# ControleCarga.net
KiCad netlist of a schematic drawn in EAGLE
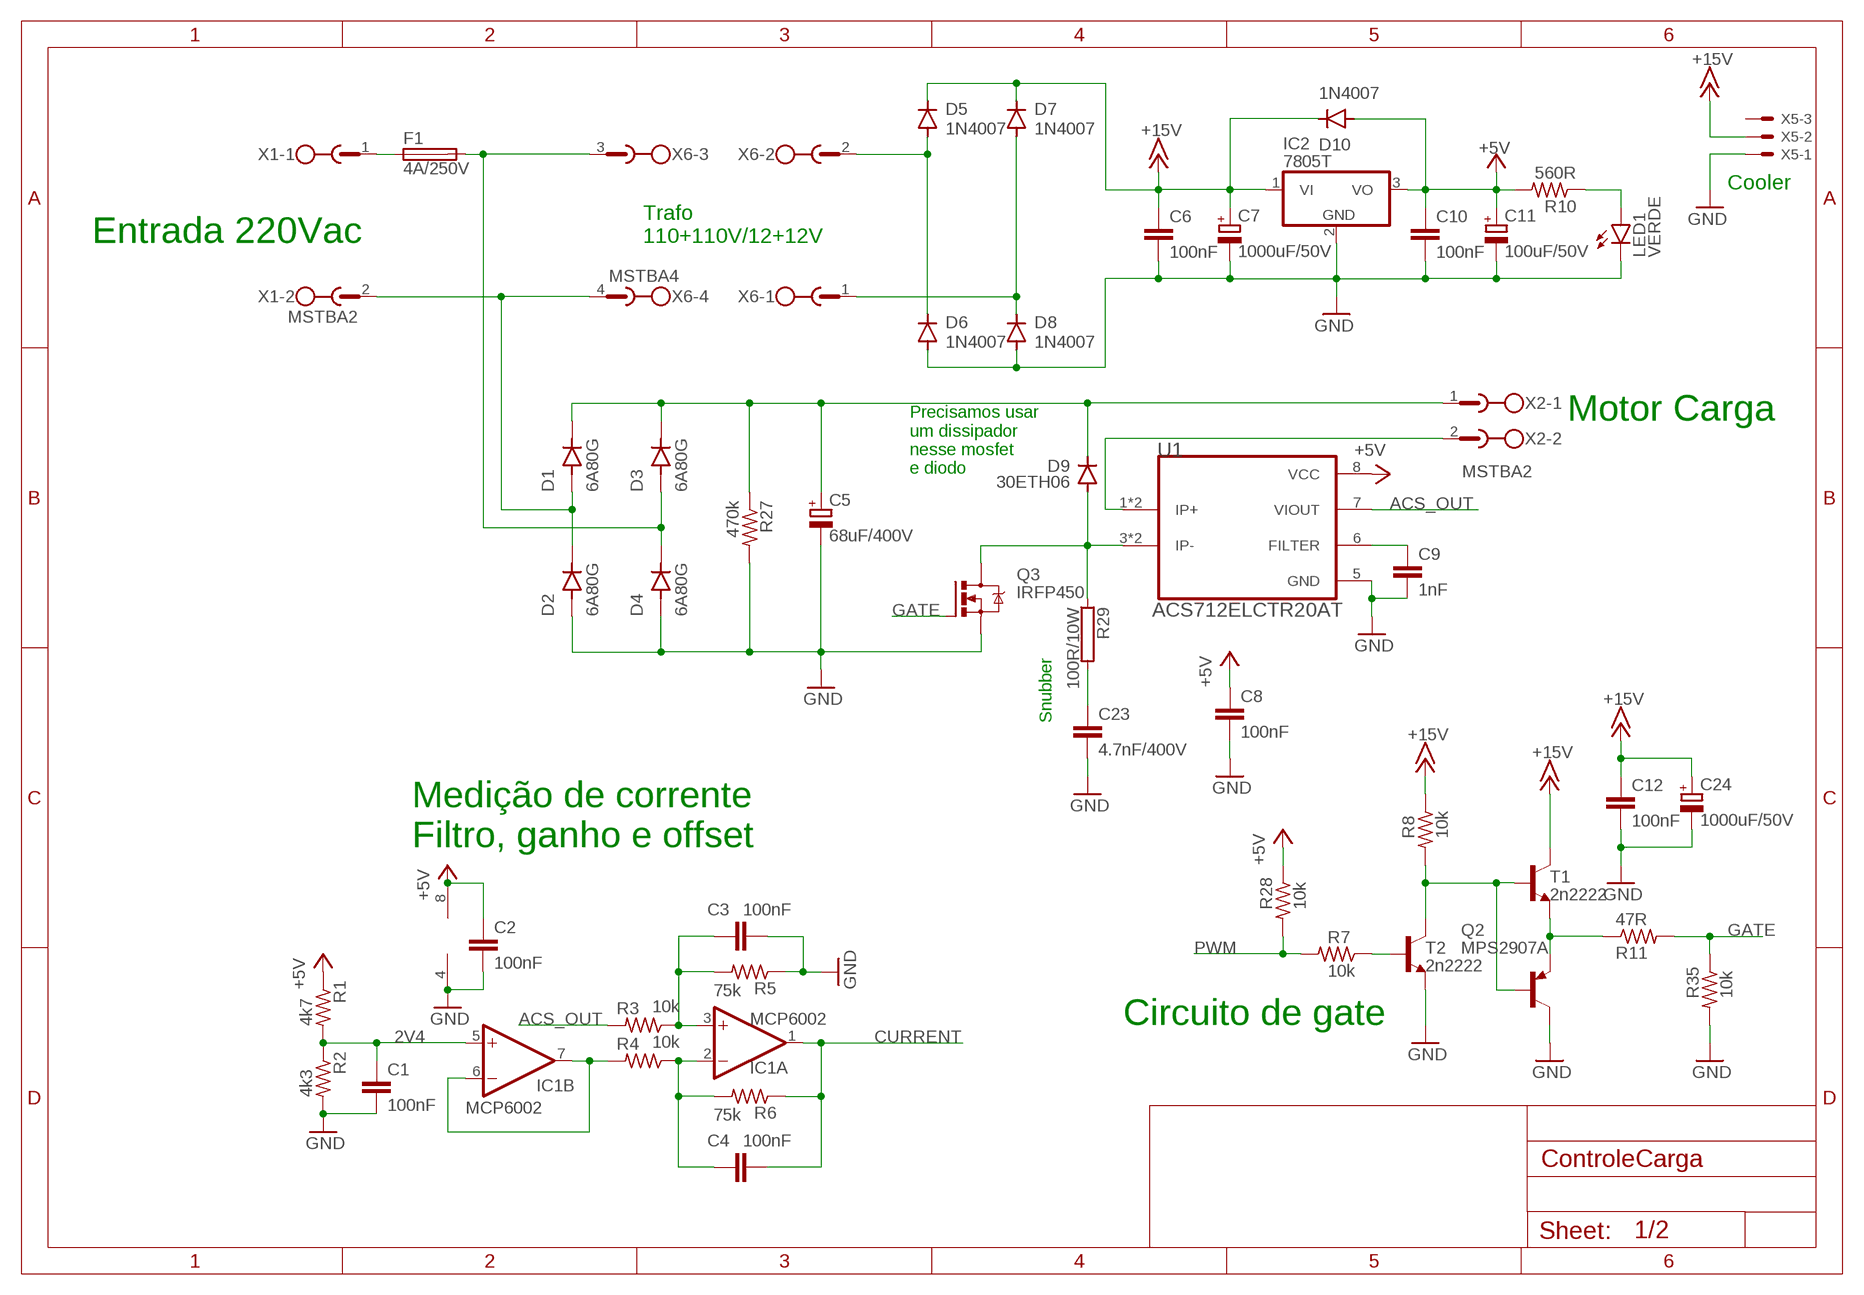
[diagram p0: schematic, sheet 1]
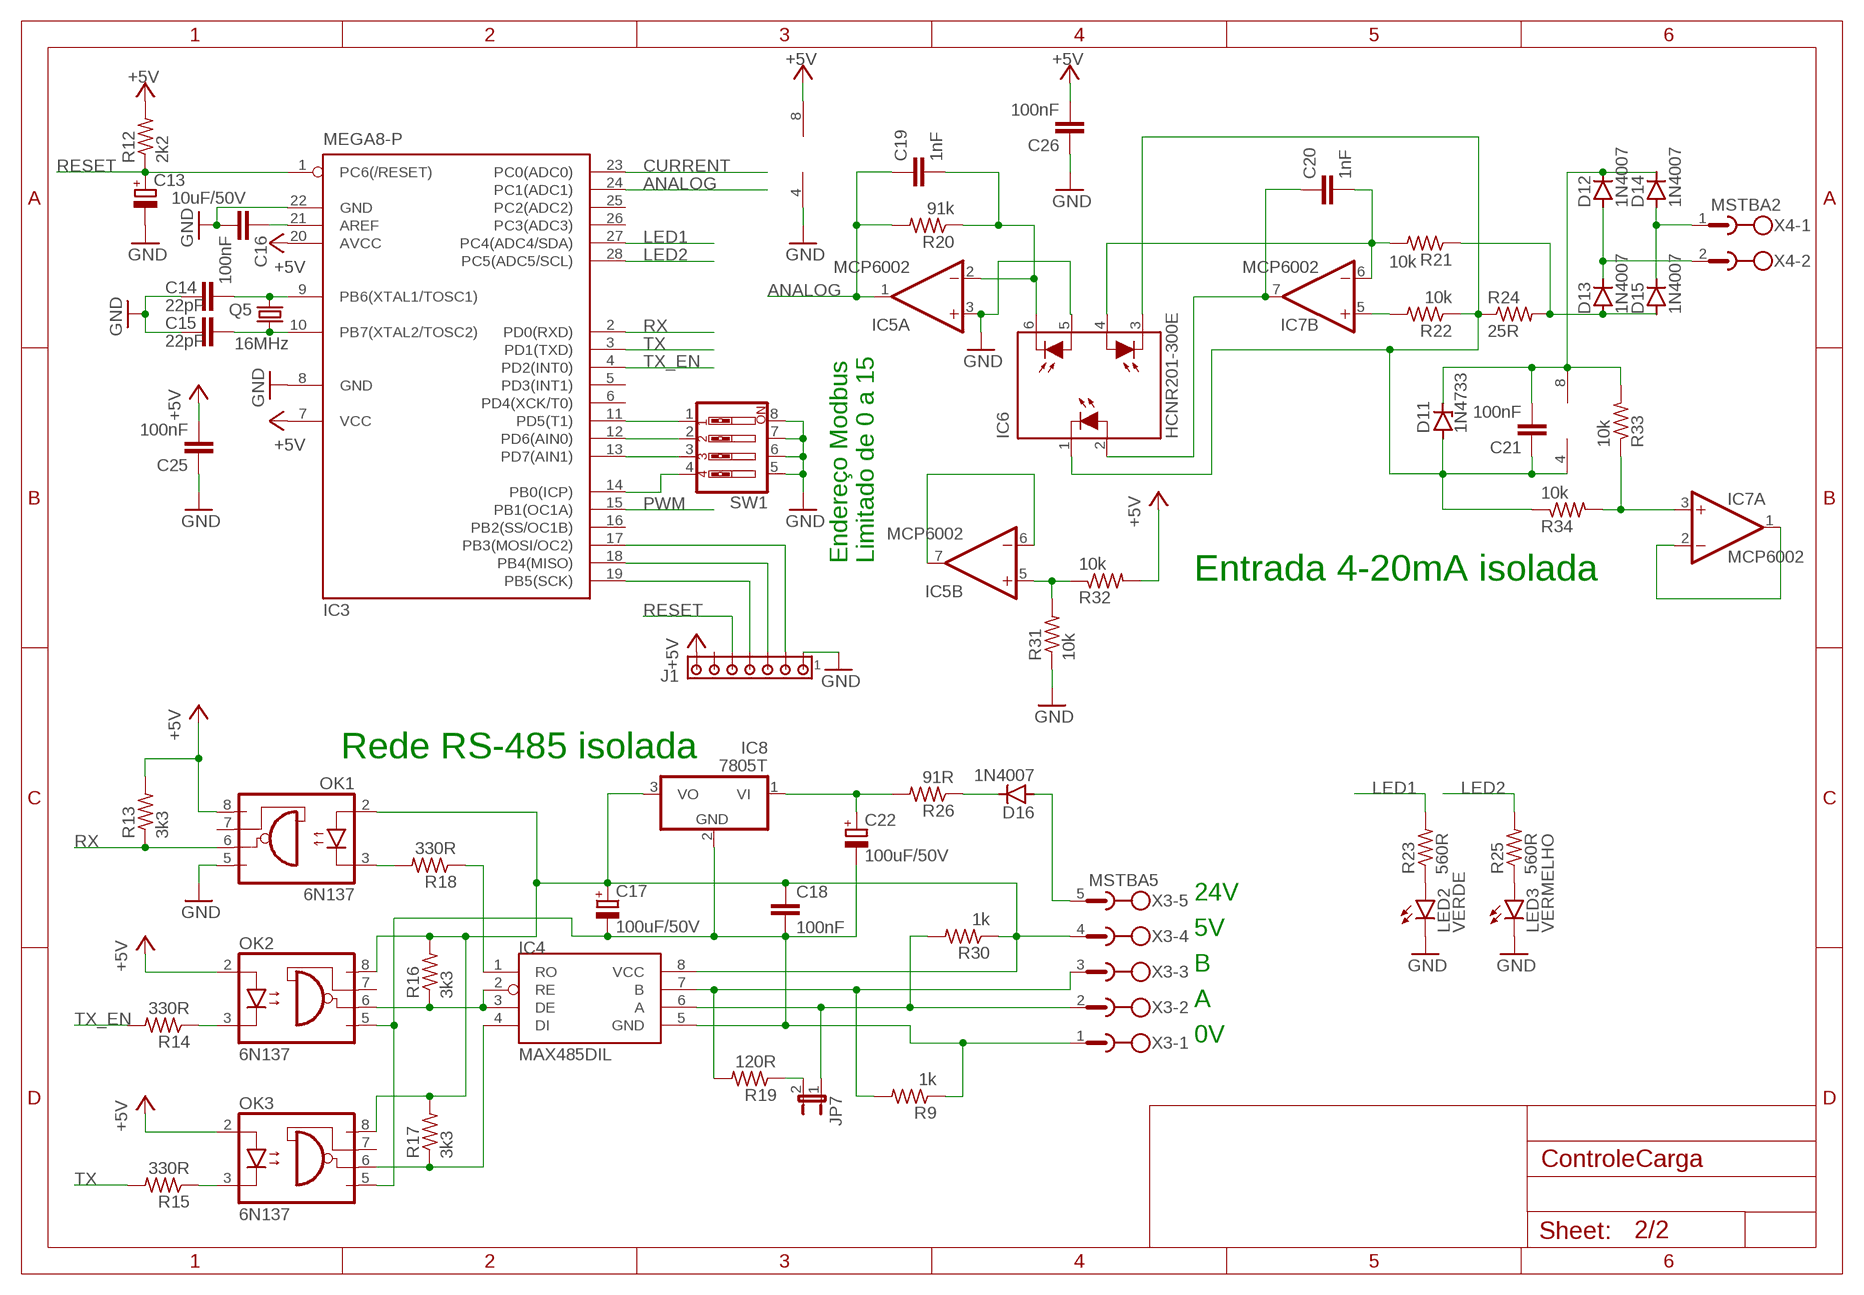
[diagram p1: schematic, sheet 2]

(export (version "E")
  (design (tool "Eeschema 10.0.6"))
  (components
    (comp (ref "C13")
      (value "10uF/50V")
      (footprint "eagle-import:E2-5")
      (libsource (lib "eagle-import") (part "CPOL-EUE2-5"))
    )
    (comp (ref "C14")
      (value "22pF")
      (footprint "eagle-import:C025-024X044")
      (libsource (lib "eagle-import") (part "C-EU025-024X044"))
    )
    (comp (ref "C15")
      (value "22pF")
      (footprint "eagle-import:C025-024X044")
      (libsource (lib "eagle-import") (part "C-EU025-024X044"))
    )
    (comp (ref "C16")
      (value "100nF")
      (footprint "eagle-import:C050-025X075")
      (libsource (lib "eagle-import") (part "C-EU050-025X075"))
    )
    (comp (ref "C17")
      (value "100uF/50V")
      (footprint "eagle-import:E3,5-8")
      (libsource (lib "eagle-import") (part "CPOL-EUE3.5-8"))
    )
    (comp (ref "C18")
      (value "100nF")
      (footprint "eagle-import:C050-025X075")
      (libsource (lib "eagle-import") (part "C-EU050-025X075"))
    )
    (comp (ref "C19")
      (value "1nF")
      (footprint "eagle-import:C025-024X044")
      (libsource (lib "eagle-import") (part "C-EU025-024X044"))
    )
    (comp (ref "C20")
      (value "1nF")
      (footprint "eagle-import:C025-024X044")
      (libsource (lib "eagle-import") (part "C-EU025-024X044"))
    )
    (comp (ref "C21")
      (value "100nF")
      (footprint "eagle-import:C050-025X075")
      (libsource (lib "eagle-import") (part "C-EU050-025X075"))
    )
    (comp (ref "C22")
      (value "100uF/50V")
      (footprint "eagle-import:E3,5-8")
      (libsource (lib "eagle-import") (part "CPOL-EUE3.5-8"))
    )
    (comp (ref "C25")
      (value "100nF")
      (footprint "eagle-import:C050-025X075")
      (libsource (lib "eagle-import") (part "C-EU050-025X075"))
    )
    (comp (ref "C26")
      (value "100nF")
      (footprint "eagle-import:C050-025X075")
      (libsource (lib "eagle-import") (part "C-EU050-025X075"))
    )
    (comp (ref "D11")
      (value "1N4733")
      (footprint "eagle-import:DO41Z10")
      (libsource (lib "eagle-import") (part "1N4728"))
    )
    (comp (ref "D12")
      (value "1N4007")
      (footprint "eagle-import:DO41-10")
      (libsource (lib "eagle-import") (part "1N4004"))
    )
    (comp (ref "D13")
      (value "1N4007")
      (footprint "eagle-import:DO41-10")
      (libsource (lib "eagle-import") (part "1N4004"))
    )
    (comp (ref "D14")
      (value "1N4007")
      (footprint "eagle-import:DO41-10")
      (libsource (lib "eagle-import") (part "1N4004"))
    )
    (comp (ref "D15")
      (value "1N4007")
      (footprint "eagle-import:DO41-10")
      (libsource (lib "eagle-import") (part "1N4004"))
    )
    (comp (ref "D16")
      (value "1N4007")
      (footprint "eagle-import:DO41-10")
      (libsource (lib "eagle-import") (part "1N4004"))
    )
    (comp (ref "IC3")
      (value "MEGA8-P")
      (footprint "eagle-import:DIL28-3")
      (libsource (lib "eagle-import") (part "MEGA8-P"))
    )
    (comp (ref "IC4")
      (value "MAX485DIL")
      (footprint "eagle-import:DIL08")
      (fields (field (name "MF") "Maxim Integrated") (field (name "MP") "MAX485"))
      (libsource (lib "eagle-import") (part "MAX485DIL"))
    )
    (comp (ref "IC5")
      (value "MCP6002")
      (footprint "eagle-import:SO08")
      (libsource (lib "eagle-import") (part "MCP602SN"))
    )
    (comp (ref "IC6")
      (value "HCNR201-300E")
      (footprint "eagle-import:DIP8-400")
      (libsource (lib "eagle-import") (part "HCNR20-300E1"))
    )
    (comp (ref "IC7")
      (value "MCP6002")
      (footprint "eagle-import:SO08")
      (libsource (lib "eagle-import") (part "MCP602SN"))
    )
    (comp (ref "IC8")
      (value "7805T")
      (footprint "eagle-import:TO220H")
      (libsource (lib "eagle-import") (part "78T05"))
    )
    (comp (ref "J1")
      (value "MTA07-100")
      (footprint "eagle-import:10X07MTA")
      (libsource (lib "eagle-import") (part "MTA07-100"))
    )
    (comp (ref "JP7")
      (value "JP1E")
      (footprint "eagle-import:JP1")
      (libsource (lib "eagle-import") (part "JP1E"))
    )
    (comp (ref "LED2")
      (value "VERDE")
      (footprint "eagle-import:LED5MM")
      (libsource (lib "eagle-import") (part "LED5MM"))
    )
    (comp (ref "LED3")
      (value "VERMELHO")
      (footprint "eagle-import:LED5MM")
      (libsource (lib "eagle-import") (part "LED5MM"))
    )
    (comp (ref "OK1")
      (value "6N137")
      (footprint "eagle-import:DIL08")
      (libsource (lib "eagle-import") (part "6N137"))
    )
    (comp (ref "OK2")
      (value "6N137")
      (footprint "eagle-import:DIL08")
      (libsource (lib "eagle-import") (part "6N137"))
    )
    (comp (ref "OK3")
      (value "6N137")
      (footprint "eagle-import:DIL08")
      (libsource (lib "eagle-import") (part "6N137"))
    )
    (comp (ref "Q5")
      (value "16MHz")
      (footprint "eagle-import:HC49_S")
      (libsource (lib "eagle-import") (part "CRYSTALHC49S"))
    )
    (comp (ref "R9")
      (value "1k")
      (footprint "eagle-import:0207_10")
      (libsource (lib "eagle-import") (part "R-US_0207/10"))
    )
    (comp (ref "R12")
      (value "2k2")
      (footprint "eagle-import:0207_10")
      (libsource (lib "eagle-import") (part "R-US_0207/10"))
    )
    (comp (ref "R13")
      (value "3k3")
      (footprint "eagle-import:0207_10")
      (libsource (lib "eagle-import") (part "R-US_0207/10"))
    )
    (comp (ref "R14")
      (value "330R")
      (footprint "eagle-import:0207_10")
      (libsource (lib "eagle-import") (part "R-US_0207/10"))
    )
    (comp (ref "R15")
      (value "330R")
      (footprint "eagle-import:0207_10")
      (libsource (lib "eagle-import") (part "R-US_0207/10"))
    )
    (comp (ref "R16")
      (value "3k3")
      (footprint "eagle-import:0207_10")
      (libsource (lib "eagle-import") (part "R-US_0207/10"))
    )
    (comp (ref "R17")
      (value "3k3")
      (footprint "eagle-import:0207_10")
      (libsource (lib "eagle-import") (part "R-US_0207/10"))
    )
    (comp (ref "R18")
      (value "330R")
      (footprint "eagle-import:0207_10")
      (libsource (lib "eagle-import") (part "R-US_0207/10"))
    )
    (comp (ref "R19")
      (value "120R")
      (footprint "eagle-import:0207_10")
      (libsource (lib "eagle-import") (part "R-US_0207/10"))
    )
    (comp (ref "R20")
      (value "91k")
      (footprint "eagle-import:0207_10")
      (libsource (lib "eagle-import") (part "R-US_0207/10"))
    )
    (comp (ref "R21")
      (value "10k")
      (footprint "eagle-import:0207_10")
      (libsource (lib "eagle-import") (part "R-US_0207/10"))
    )
    (comp (ref "R22")
      (value "10k")
      (footprint "eagle-import:0207_10")
      (libsource (lib "eagle-import") (part "R-US_0207/10"))
    )
    (comp (ref "R23")
      (value "560R")
      (footprint "eagle-import:0207_10")
      (libsource (lib "eagle-import") (part "R-US_0207/10"))
    )
    (comp (ref "R24")
      (value "25R")
      (footprint "eagle-import:0207_10")
      (libsource (lib "eagle-import") (part "R-US_0207/10"))
    )
    (comp (ref "R25")
      (value "560R")
      (footprint "eagle-import:0207_10")
      (libsource (lib "eagle-import") (part "R-US_0207/10"))
    )
    (comp (ref "R26")
      (value "91R")
      (footprint "eagle-import:0207_10")
      (libsource (lib "eagle-import") (part "R-US_0207/10"))
    )
    (comp (ref "R30")
      (value "1k")
      (footprint "eagle-import:0207_10")
      (libsource (lib "eagle-import") (part "R-US_0207/10"))
    )
    (comp (ref "R31")
      (value "10k")
      (footprint "eagle-import:0207_10")
      (libsource (lib "eagle-import") (part "R-US_0207/10"))
    )
    (comp (ref "R32")
      (value "10k")
      (footprint "eagle-import:0207_10")
      (libsource (lib "eagle-import") (part "R-US_0207/10"))
    )
    (comp (ref "R33")
      (value "10k")
      (footprint "eagle-import:0207_10")
      (libsource (lib "eagle-import") (part "R-US_0207/10"))
    )
    (comp (ref "R34")
      (value "10k")
      (footprint "eagle-import:0207_10")
      (libsource (lib "eagle-import") (part "R-US_0207/10"))
    )
    (comp (ref "SW1")
      (value "SW_DIP-4")
      (footprint "eagle-import:EDG-04")
      (libsource (lib "eagle-import") (part "SW_DIP-4"))
    )
    (comp (ref "X3")
      (value "MSTBA5")
      (footprint "eagle-import:MSTBA5")
      (fields (field (name "MPN") "1757271"))
      (libsource (lib "eagle-import") (part "MSTBA5"))
    )
    (comp (ref "X4")
      (value "MSTBA2")
      (footprint "eagle-import:MSTBA2")
      (fields (field (name "MF") "FARNELL") (field (name "MPN") "1757242"))
      (libsource (lib "eagle-import") (part "MSTBA2"))
    )
    (comp (ref "C1")
      (value "100nF")
      (footprint "eagle-import:C050-025X075")
      (libsource (lib "eagle-import") (part "C-EU050-025X075"))
    )
    (comp (ref "C2")
      (value "100nF")
      (footprint "eagle-import:C050-025X075")
      (libsource (lib "eagle-import") (part "C-EU050-025X075"))
    )
    (comp (ref "C3")
      (value "100nF")
      (footprint "eagle-import:C050-025X075")
      (libsource (lib "eagle-import") (part "C-EU050-025X075"))
    )
    (comp (ref "C4")
      (value "100nF")
      (footprint "eagle-import:C050-025X075")
      (libsource (lib "eagle-import") (part "C-EU050-025X075"))
    )
    (comp (ref "C5")
      (value "68uF/400V")
      (footprint "eagle-import:E7,5-18")
      (libsource (lib "eagle-import") (part "CPOL-EUE7.5-18"))
    )
    (comp (ref "C6")
      (value "100nF")
      (footprint "eagle-import:C050-025X075")
      (libsource (lib "eagle-import") (part "C-EU050-025X075"))
    )
    (comp (ref "C7")
      (value "1000uF/50V")
      (footprint "eagle-import:E5-13")
      (libsource (lib "eagle-import") (part "CPOL-EUE5-13"))
    )
    (comp (ref "C8")
      (value "100nF")
      (footprint "eagle-import:C050-025X075")
      (libsource (lib "eagle-import") (part "C-EU050-025X075"))
    )
    (comp (ref "C9")
      (value "1nF")
      (footprint "eagle-import:C025-024X044")
      (libsource (lib "eagle-import") (part "C-EU025-024X044"))
    )
    (comp (ref "C10")
      (value "100nF")
      (footprint "eagle-import:C050-025X075")
      (libsource (lib "eagle-import") (part "C-EU050-025X075"))
    )
    (comp (ref "C11")
      (value "100uF/50V")
      (footprint "eagle-import:E3,5-8")
      (libsource (lib "eagle-import") (part "CPOL-EUE3.5-8"))
    )
    (comp (ref "C12")
      (value "100nF")
      (footprint "eagle-import:C050-025X075")
      (libsource (lib "eagle-import") (part "C-EU050-025X075"))
    )
    (comp (ref "C23")
      (value "4.7nF/400V")
      (footprint "eagle-import:C102-043X133")
      (libsource (lib "eagle-import") (part "C-EU102-043X133"))
    )
    (comp (ref "C24")
      (value "1000uF/50V")
      (footprint "eagle-import:E5-13")
      (libsource (lib "eagle-import") (part "CPOL-EUE5-13"))
    )
    (comp (ref "D1")
      (value "6A80G")
      (footprint "eagle-import:DIOAD1950W125L885D700")
      (fields (field (name "MF") "Taiwan Semiconductor"))
      (libsource (lib "eagle-import") (part "6A80G"))
    )
    (comp (ref "D2")
      (value "6A80G")
      (footprint "eagle-import:DIOAD1950W125L885D700")
      (fields (field (name "MF") "Taiwan Semiconductor"))
      (libsource (lib "eagle-import") (part "6A80G"))
    )
    (comp (ref "D3")
      (value "6A80G")
      (footprint "eagle-import:DIOAD1950W125L885D700")
      (fields (field (name "MF") "Taiwan Semiconductor"))
      (libsource (lib "eagle-import") (part "6A80G"))
    )
    (comp (ref "D4")
      (value "6A80G")
      (footprint "eagle-import:DIOAD1950W125L885D700")
      (fields (field (name "MF") "Taiwan Semiconductor"))
      (libsource (lib "eagle-import") (part "6A80G"))
    )
    (comp (ref "D5")
      (value "1N4007")
      (footprint "eagle-import:DO41-10")
      (libsource (lib "eagle-import") (part "1N4004"))
    )
    (comp (ref "D6")
      (value "1N4007")
      (footprint "eagle-import:DO41-10")
      (libsource (lib "eagle-import") (part "1N4004"))
    )
    (comp (ref "D7")
      (value "1N4007")
      (footprint "eagle-import:DO41-10")
      (libsource (lib "eagle-import") (part "1N4004"))
    )
    (comp (ref "D8")
      (value "1N4007")
      (footprint "eagle-import:DO41-10")
      (libsource (lib "eagle-import") (part "1N4004"))
    )
    (comp (ref "D9")
      (value "30ETH06")
      (footprint "eagle-import:TO220ACS")
      (libsource (lib "eagle-import") (part "BYT08P"))
    )
    (comp (ref "D10")
      (value "1N4007")
      (footprint "eagle-import:DO41-10")
      (libsource (lib "eagle-import") (part "1N4004"))
    )
    (comp (ref "F1")
      (value "4A/250V")
      (footprint "eagle-import:SH22")
      (libsource (lib "eagle-import") (part "FUSESH22"))
    )
    (comp (ref "IC1")
      (value "MCP6002")
      (footprint "eagle-import:SO08")
      (libsource (lib "eagle-import") (part "MCP602SN"))
    )
    (comp (ref "IC2")
      (value "7805T")
      (footprint "eagle-import:TO220H")
      (libsource (lib "eagle-import") (part "78T05"))
    )
    (comp (ref "LED1")
      (value "VERDE")
      (footprint "eagle-import:LED5MM")
      (libsource (lib "eagle-import") (part "LED5MM"))
    )
    (comp (ref "Q2")
      (value "MPS2907A")
      (footprint "eagle-import:TO92-CBE")
      (libsource (lib "eagle-import") (part "MPS2907A"))
    )
    (comp (ref "Q3")
      (value "IRFP450")
      (footprint "eagle-import:TO247BV")
      (libsource (lib "eagle-import") (part "IRFPC40"))
    )
    (comp (ref "R1")
      (value "4k7")
      (footprint "eagle-import:0207_10")
      (libsource (lib "eagle-import") (part "R-US_0207/10"))
    )
    (comp (ref "R2")
      (value "4k3")
      (footprint "eagle-import:0207_10")
      (libsource (lib "eagle-import") (part "R-US_0207/10"))
    )
    (comp (ref "R3")
      (value "10k")
      (footprint "eagle-import:0207_10")
      (libsource (lib "eagle-import") (part "R-US_0207/10"))
    )
    (comp (ref "R4")
      (value "10k")
      (footprint "eagle-import:0207_10")
      (libsource (lib "eagle-import") (part "R-US_0207/10"))
    )
    (comp (ref "R5")
      (value "75k")
      (footprint "eagle-import:0207_10")
      (libsource (lib "eagle-import") (part "R-US_0207/10"))
    )
    (comp (ref "R6")
      (value "75k")
      (footprint "eagle-import:0207_10")
      (libsource (lib "eagle-import") (part "R-US_0207/10"))
    )
    (comp (ref "R7")
      (value "10k")
      (footprint "eagle-import:0207_10")
      (libsource (lib "eagle-import") (part "R-US_0207/10"))
    )
    (comp (ref "R8")
      (value "10k")
      (footprint "eagle-import:0207_10")
      (libsource (lib "eagle-import") (part "R-US_0207/10"))
    )
    (comp (ref "R10")
      (value "560R")
      (footprint "eagle-import:0207_10")
      (libsource (lib "eagle-import") (part "R-US_0207/10"))
    )
    (comp (ref "R11")
      (value "47R")
      (footprint "eagle-import:0207_10")
      (libsource (lib "eagle-import") (part "R-US_0207/10"))
    )
    (comp (ref "R27")
      (value "470k")
      (footprint "eagle-import:0207_10")
      (libsource (lib "eagle-import") (part "R-US_0207/10"))
    )
    (comp (ref "R28")
      (value "10k")
      (footprint "eagle-import:0207_10")
      (libsource (lib "eagle-import") (part "R-US_0207/10"))
    )
    (comp (ref "R29")
      (value "100R/10W")
      (footprint "eagle-import:KH216-8")
      (libsource (lib "eagle-import") (part "RKH216-8"))
    )
    (comp (ref "R35")
      (value "10k")
      (footprint "eagle-import:0207_10")
      (libsource (lib "eagle-import") (part "R-US_0207/10"))
    )
    (comp (ref "T1")
      (value "2n2222")
      (footprint "eagle-import:TO92-EBC")
      (libsource (lib "eagle-import") (part "-NPN-TO92-EBC2N2222"))
    )
    (comp (ref "T2")
      (value "2n2222")
      (footprint "eagle-import:TO92-EBC")
      (libsource (lib "eagle-import") (part "-NPN-TO92-EBC2N2222"))
    )
    (comp (ref "U1")
      (value "ACS712ELCTR20AT")
      (footprint "eagle-import:SOIC127P600X175-8N")
      (fields (field (name "MF") "Allegro") (field (name "MP") "ACS712ELCTR-30A-T"))
      (libsource (lib "eagle-import") (part "ACS712ELCTR30AT"))
    )
    (comp (ref "X1")
      (value "MSTBA2")
      (footprint "eagle-import:MSTBA2")
      (fields (field (name "MF") "FARNELL") (field (name "MPN") "1757242"))
      (libsource (lib "eagle-import") (part "MSTBA2"))
    )
    (comp (ref "X2")
      (value "MSTBA2")
      (footprint "eagle-import:MSTBA2")
      (fields (field (name "MF") "FARNELL") (field (name "MPN") "1757242"))
      (libsource (lib "eagle-import") (part "MSTBA2"))
    )
    (comp (ref "X5")
      (value "KK-156-3")
      (footprint "eagle-import:KK-156-3")
      (fields (field (name "MF") "MOLEX"))
      (libsource (lib "eagle-import") (part "KK-156-3"))
    )
    (comp (ref "X6")
      (value "MSTBA4")
      (footprint "eagle-import:MSTBA4")
      (fields (field (name "MF") "FARNELL") (field (name "MPN") "1757268"))
      (libsource (lib "eagle-import") (part "MSTBA4"))
    )
  )
  (nets
    (net (code "1") (name "+5V") (class "Default")
      (node (ref "C10") (pin "1") (pinfunction "1_1") (pintype "passive"))
      (node (ref "C11") (pin "+") (pinfunction "+_+") (pintype "passive"))
      (node (ref "C2") (pin "1") (pinfunction "1_1") (pintype "passive"))
      (node (ref "C25") (pin "2") (pinfunction "2_2") (pintype "passive"))
      (node (ref "C26") (pin "2") (pinfunction "2_2") (pintype "passive"))
      (node (ref "C8") (pin "1") (pinfunction "1_1") (pintype "passive"))
      (node (ref "D10") (pin "A") (pinfunction "A_A") (pintype "passive"))
      (node (ref "IC1") (pin "8") (pinfunction "V+_8") (pintype "power_in"))
      (node (ref "IC2") (pin "3") (pinfunction "VO_3") (pintype "passive"))
      (node (ref "IC3") (pin "20") (pinfunction "AVCC_20") (pintype "power_in"))
      (node (ref "IC3") (pin "7") (pinfunction "VCC_7") (pintype "power_in"))
      (node (ref "IC5") (pin "8") (pinfunction "V+_8") (pintype "power_in"))
      (node (ref "J1") (pin "7") (pinfunction "7_7") (pintype "passive"))
      (node (ref "OK1") (pin "8") (pinfunction "VCC_8") (pintype "passive"))
      (node (ref "OK2") (pin "2") (pinfunction "A_2") (pintype "passive"))
      (node (ref "OK3") (pin "2") (pinfunction "A_2") (pintype "passive"))
      (node (ref "R1") (pin "1") (pinfunction "1_1") (pintype "passive"))
      (node (ref "R10") (pin "2") (pinfunction "2_2") (pintype "passive"))
      (node (ref "R12") (pin "2") (pinfunction "2_2") (pintype "passive"))
      (node (ref "R13") (pin "2") (pinfunction "2_2") (pintype "passive"))
      (node (ref "R28") (pin "1") (pinfunction "1_1") (pintype "passive"))
      (node (ref "R32") (pin "2") (pinfunction "2_2") (pintype "passive"))
      (node (ref "U1") (pin "8") (pinfunction "VCC_8") (pintype "power_in"))
    )
    (net (code "2") (name "+15V") (class "Default")
      (node (ref "C12") (pin "1") (pinfunction "1_1") (pintype "passive"))
      (node (ref "C24") (pin "+") (pinfunction "+_+") (pintype "passive"))
      (node (ref "C6") (pin "1") (pinfunction "1_1") (pintype "passive"))
      (node (ref "C7") (pin "+") (pinfunction "+_+") (pintype "passive"))
      (node (ref "D10") (pin "C") (pinfunction "C_C") (pintype "passive"))
      (node (ref "D5") (pin "C") (pinfunction "C_C") (pintype "passive"))
      (node (ref "D7") (pin "C") (pinfunction "C_C") (pintype "passive"))
      (node (ref "IC2") (pin "1") (pinfunction "VI_1") (pintype "input"))
      (node (ref "R8") (pin "1") (pinfunction "1_1") (pintype "passive"))
      (node (ref "T1") (pin "C") (pinfunction "C_C") (pintype "passive"))
      (node (ref "X5") (pin "2") (pinfunction "S_2") (pintype "passive"))
    )
    (net (code "3") (name "2V4") (class "Default")
      (node (ref "C1") (pin "1") (pinfunction "1_1") (pintype "passive"))
      (node (ref "IC1") (pin "5") (pinfunction "+IN_5") (pintype "input"))
      (node (ref "R1") (pin "2") (pinfunction "2_2") (pintype "passive"))
      (node (ref "R2") (pin "1") (pinfunction "1_1") (pintype "passive"))
    )
    (net (code "4") (name "ACS_OUT") (class "Default")
      (node (ref "R3") (pin "2") (pinfunction "2_2") (pintype "passive"))
      (node (ref "U1") (pin "7") (pinfunction "VIOUT_7") (pintype "output"))
    )
    (net (code "5") (name "ANALOG") (class "Default")
      (node (ref "C19") (pin "1") (pinfunction "1_1") (pintype "passive"))
      (node (ref "IC3") (pin "24") (pinfunction "PC1(ADC1)_24") (pintype "bidirectional"))
      (node (ref "IC5") (pin "1") (pinfunction "OUT_1") (pintype "output"))
      (node (ref "R20") (pin "2") (pinfunction "2_2") (pintype "passive"))
    )
    (net (code "6") (name "CURRENT") (class "Default")
      (node (ref "C4") (pin "2") (pinfunction "2_2") (pintype "passive"))
      (node (ref "IC1") (pin "1") (pinfunction "OUT_1") (pintype "output"))
      (node (ref "IC3") (pin "23") (pinfunction "PC0(ADC0)_23") (pintype "bidirectional"))
      (node (ref "R6") (pin "1") (pinfunction "1_1") (pintype "passive"))
    )
    (net (code "7") (name "GATE") (class "Default")
      (node (ref "Q3") (pin "G") (pinfunction "G_G") (pintype "passive"))
      (node (ref "R11") (pin "2") (pinfunction "2_2") (pintype "passive"))
      (node (ref "R35") (pin "1") (pinfunction "1_1") (pintype "passive"))
    )
    (net (code "8") (name "GND") (class "Default")
      (node (ref "C1") (pin "2") (pinfunction "2_2") (pintype "passive"))
      (node (ref "C10") (pin "2") (pinfunction "2_2") (pintype "passive"))
      (node (ref "C11") (pin "-") (pinfunction "-_-") (pintype "passive"))
      (node (ref "C12") (pin "2") (pinfunction "2_2") (pintype "passive"))
      (node (ref "C13") (pin "-") (pinfunction "-_-") (pintype "passive"))
      (node (ref "C14") (pin "2") (pinfunction "2_2") (pintype "passive"))
      (node (ref "C15") (pin "2") (pinfunction "2_2") (pintype "passive"))
      (node (ref "C16") (pin "2") (pinfunction "2_2") (pintype "passive"))
      (node (ref "C2") (pin "2") (pinfunction "2_2") (pintype "passive"))
      (node (ref "C23") (pin "2") (pinfunction "2_2") (pintype "passive"))
      (node (ref "C24") (pin "-") (pinfunction "-_-") (pintype "passive"))
      (node (ref "C25") (pin "1") (pinfunction "1_1") (pintype "passive"))
      (node (ref "C26") (pin "1") (pinfunction "1_1") (pintype "passive"))
      (node (ref "C3") (pin "2") (pinfunction "2_2") (pintype "passive"))
      (node (ref "C5") (pin "-") (pinfunction "-_-") (pintype "passive"))
      (node (ref "C6") (pin "2") (pinfunction "2_2") (pintype "passive"))
      (node (ref "C7") (pin "-") (pinfunction "-_-") (pintype "passive"))
      (node (ref "C8") (pin "2") (pinfunction "2_2") (pintype "passive"))
      (node (ref "C9") (pin "2") (pinfunction "2_2") (pintype "passive"))
      (node (ref "D2") (pin "A") (pinfunction "A_A") (pintype "passive"))
      (node (ref "D4") (pin "A") (pinfunction "A_A") (pintype "passive"))
      (node (ref "D6") (pin "A") (pinfunction "A_A") (pintype "passive"))
      (node (ref "D8") (pin "A") (pinfunction "A_A") (pintype "passive"))
      (node (ref "IC1") (pin "4") (pinfunction "V-_4") (pintype "power_in"))
      (node (ref "IC2") (pin "2") (pinfunction "GND_2") (pintype "passive"))
      (node (ref "IC3") (pin "22") (pinfunction "GND_22") (pintype "power_in"))
      (node (ref "IC3") (pin "8") (pinfunction "GND_8") (pintype "power_in"))
      (node (ref "IC5") (pin "3") (pinfunction "+IN_3") (pintype "input"))
      (node (ref "IC5") (pin "4") (pinfunction "V-_4") (pintype "power_in"))
      (node (ref "IC6") (pin "5") (pinfunction "A2_5") (pintype "passive"))
      (node (ref "J1") (pin "1") (pinfunction "1_1") (pintype "passive"))
      (node (ref "LED1") (pin "K") (pinfunction "C_K") (pintype "passive"))
      (node (ref "LED2") (pin "K") (pinfunction "C_K") (pintype "passive"))
      (node (ref "LED3") (pin "K") (pinfunction "C_K") (pintype "passive"))
      (node (ref "OK1") (pin "5") (pinfunction "GND_5") (pintype "passive"))
      (node (ref "Q2") (pin "C") (pinfunction "C_C") (pintype "passive"))
      (node (ref "Q3") (pin "S") (pinfunction "S_S") (pintype "passive"))
      (node (ref "R2") (pin "2") (pinfunction "2_2") (pintype "passive"))
      (node (ref "R27") (pin "2") (pinfunction "2_2") (pintype "passive"))
      (node (ref "R31") (pin "1") (pinfunction "1_1") (pintype "passive"))
      (node (ref "R35") (pin "2") (pinfunction "2_2") (pintype "passive"))
      (node (ref "R5") (pin "1") (pinfunction "1_1") (pintype "passive"))
      (node (ref "SW1") (pin "5") (pinfunction "5_5") (pintype "passive"))
      (node (ref "SW1") (pin "6") (pinfunction "6_6") (pintype "passive"))
      (node (ref "SW1") (pin "7") (pinfunction "7_7") (pintype "passive"))
      (node (ref "SW1") (pin "8") (pinfunction "8_8") (pintype "passive"))
      (node (ref "T2") (pin "E") (pinfunction "E_E") (pintype "passive"))
      (node (ref "U1") (pin "5") (pinfunction "GND_5") (pintype "power_in"))
      (node (ref "X5") (pin "1") (pinfunction "S_1") (pintype "passive"))
    )
    (net (code "9") (name "LED1") (class "Default")
      (node (ref "IC3") (pin "27") (pinfunction "PC4(ADC4/SDA)_27") (pintype "bidirectional"))
      (node (ref "R23") (pin "2") (pinfunction "2_2") (pintype "passive"))
    )
    (net (code "10") (name "LED2") (class "Default")
      (node (ref "IC3") (pin "28") (pinfunction "PC5(ADC5/SCL)_28") (pintype "bidirectional"))
      (node (ref "R25") (pin "2") (pinfunction "2_2") (pintype "passive"))
    )
    (net (code "11") (name "Net-(C23-Pad1)") (class "Default")
      (node (ref "C23") (pin "1") (pinfunction "1_1") (pintype "passive"))
      (node (ref "R29") (pin "2") (pinfunction "2_2") (pintype "passive"))
    )
    (net (code "12") (name "Net-(D1-K)") (class "Default")
      (node (ref "C5") (pin "+") (pinfunction "+_+") (pintype "passive"))
      (node (ref "D1") (pin "C") (pinfunction "K_C") (pintype "passive"))
      (node (ref "D3") (pin "C") (pinfunction "K_C") (pintype "passive"))
      (node (ref "D9") (pin "C") (pinfunction "C_C") (pintype "passive"))
      (node (ref "R27") (pin "1") (pinfunction "1_1") (pintype "passive"))
      (node (ref "X2") (pin "1") (pinfunction "1_1") (pintype "passive"))
    )
    (net (code "13") (name "Net-(D2-K)") (class "Default")
      (node (ref "D1") (pin "A") (pinfunction "A_A") (pintype "passive"))
      (node (ref "D2") (pin "C") (pinfunction "K_C") (pintype "passive"))
      (node (ref "X1") (pin "2") (pinfunction "1_2") (pintype "passive"))
      (node (ref "X6") (pin "4") (pinfunction "1_4") (pintype "passive"))
    )
    (net (code "14") (name "Net-(D4-K)") (class "Default")
      (node (ref "D3") (pin "A") (pinfunction "A_A") (pintype "passive"))
      (node (ref "D4") (pin "C") (pinfunction "K_C") (pintype "passive"))
      (node (ref "F1") (pin "2") (pinfunction "2_2") (pintype "passive"))
      (node (ref "X6") (pin "3") (pinfunction "1_3") (pintype "passive"))
    )
    (net (code "15") (name "Net-(D7-PadA)") (class "Default")
      (node (ref "D7") (pin "A") (pinfunction "A_A") (pintype "passive"))
      (node (ref "D8") (pin "C") (pinfunction "C_C") (pintype "passive"))
      (node (ref "X6") (pin "1") (pinfunction "1_1") (pintype "passive"))
    )
    (net (code "16") (name "Net-(D9-PadA)") (class "Default")
      (node (ref "D9") (pin "A") (pinfunction "A_A") (pintype "passive"))
      (node (ref "Q3") (pin "D") (pinfunction "D_D") (pintype "passive"))
      (node (ref "R29") (pin "1") (pinfunction "1_1") (pintype "passive"))
      (node (ref "U1") (pin "3") (pinfunction "IP-_3") (pintype "input"))
      (node (ref "U1") (pin "4") (pinfunction "IP-_4") (pintype "input"))
    )
    (net (code "17") (name "Net-(D13-PadA)") (class "Default")
      (node (ref "D13") (pin "A") (pinfunction "A_A") (pintype "passive"))
      (node (ref "D15") (pin "A") (pinfunction "A_A") (pintype "passive"))
      (node (ref "R21") (pin "1") (pinfunction "1_1") (pintype "passive"))
      (node (ref "R24") (pin "2") (pinfunction "2_2") (pintype "passive"))
    )
    (net (code "18") (name "Net-(D14-PadA)") (class "Default")
      (node (ref "D14") (pin "A") (pinfunction "A_A") (pintype "passive"))
      (node (ref "D15") (pin "C") (pinfunction "C_C") (pintype "passive"))
      (node (ref "X4") (pin "1") (pinfunction "1_1") (pintype "passive"))
    )
    (net (code "19") (name "Net-(D16-PadC)") (class "Default")
      (node (ref "D16") (pin "C") (pinfunction "C_C") (pintype "passive"))
      (node (ref "R26") (pin "1") (pinfunction "1_1") (pintype "passive"))
    )
    (net (code "20") (name "Net-(F1-Pad1)") (class "Default")
      (node (ref "F1") (pin "1") (pinfunction "1_1") (pintype "passive"))
      (node (ref "X1") (pin "1") (pinfunction "1_1") (pintype "passive"))
    )
    (net (code "21") (name "Net-(IC1A-+IN)") (class "Default")
      (node (ref "C3") (pin "1") (pinfunction "1_1") (pintype "passive"))
      (node (ref "IC1") (pin "3") (pinfunction "+IN_3") (pintype "input"))
      (node (ref "R3") (pin "1") (pinfunction "1_1") (pintype "passive"))
      (node (ref "R5") (pin "2") (pinfunction "2_2") (pintype "passive"))
    )
    (net (code "22") (name "Net-(IC1A--IN)") (class "Default")
      (node (ref "C4") (pin "1") (pinfunction "1_1") (pintype "passive"))
      (node (ref "IC1") (pin "2") (pinfunction "-IN_2") (pintype "input"))
      (node (ref "R4") (pin "1") (pinfunction "1_1") (pintype "passive"))
      (node (ref "R6") (pin "2") (pinfunction "2_2") (pintype "passive"))
    )
    (net (code "23") (name "Net-(IC1B--IN)") (class "Default")
      (node (ref "IC1") (pin "6") (pinfunction "-IN_6") (pintype "input"))
      (node (ref "IC1") (pin "7") (pinfunction "OUT_7") (pintype "output"))
      (node (ref "R4") (pin "2") (pinfunction "2_2") (pintype "passive"))
    )
    (net (code "24") (name "Net-(IC3-AREF)") (class "Default")
      (node (ref "C16") (pin "1") (pinfunction "1_1") (pintype "passive"))
      (node (ref "IC3") (pin "21") (pinfunction "AREF_21") (pintype "passive"))
    )
    (net (code "25") (name "Net-(IC3-PB0(ICP))") (class "Default")
      (node (ref "IC3") (pin "14") (pinfunction "PB0(ICP)_14") (pintype "bidirectional"))
      (node (ref "SW1") (pin "4") (pinfunction "4_4") (pintype "passive"))
    )
    (net (code "26") (name "Net-(IC3-PB3(MOSI{slash}OC2))") (class "Default")
      (node (ref "IC3") (pin "17") (pinfunction "PB3(MOSI/OC2)_17") (pintype "bidirectional"))
      (node (ref "J1") (pin "2") (pinfunction "2_2") (pintype "passive"))
    )
    (net (code "27") (name "Net-(IC3-PB4(MISO))") (class "Default")
      (node (ref "IC3") (pin "18") (pinfunction "PB4(MISO)_18") (pintype "bidirectional"))
      (node (ref "J1") (pin "3") (pinfunction "3_3") (pintype "passive"))
    )
    (net (code "28") (name "Net-(IC3-PB5(SCK))") (class "Default")
      (node (ref "IC3") (pin "19") (pinfunction "PB5(SCK)_19") (pintype "bidirectional"))
      (node (ref "J1") (pin "4") (pinfunction "4_4") (pintype "passive"))
    )
    (net (code "29") (name "Net-(IC3-PB6(XTAL1{slash}TOSC1))") (class "Default")
      (node (ref "C14") (pin "1") (pinfunction "1_1") (pintype "passive"))
      (node (ref "IC3") (pin "9") (pinfunction "PB6(XTAL1/TOSC1)_9") (pintype "bidirectional"))
      (node (ref "Q5") (pin "2") (pinfunction "2_2") (pintype "passive"))
    )
    (net (code "30") (name "Net-(IC3-PB7(XTAL2{slash}TOSC2))") (class "Default")
      (node (ref "C15") (pin "1") (pinfunction "1_1") (pintype "passive"))
      (node (ref "IC3") (pin "10") (pinfunction "PB7(XTAL2/TOSC2)_10") (pintype "bidirectional"))
      (node (ref "Q5") (pin "1") (pinfunction "1_1") (pintype "passive"))
    )
    (net (code "31") (name "Net-(IC3-PD5(T1))") (class "Default")
      (node (ref "IC3") (pin "11") (pinfunction "PD5(T1)_11") (pintype "bidirectional"))
      (node (ref "SW1") (pin "1") (pinfunction "1_1") (pintype "passive"))
    )
    (net (code "32") (name "Net-(IC3-PD6(AIN0))") (class "Default")
      (node (ref "IC3") (pin "12") (pinfunction "PD6(AIN0)_12") (pintype "bidirectional"))
      (node (ref "SW1") (pin "2") (pinfunction "2_2") (pintype "passive"))
    )
    (net (code "33") (name "Net-(IC3-PD7(AIN1))") (class "Default")
      (node (ref "IC3") (pin "13") (pinfunction "PD7(AIN1)_13") (pintype "bidirectional"))
      (node (ref "SW1") (pin "3") (pinfunction "3_3") (pintype "passive"))
    )
    (net (code "34") (name "Net-(IC4-A)") (class "Default")
      (node (ref "IC4") (pin "6") (pinfunction "A_6") (pintype "bidirectional"))
      (node (ref "JP7") (pin "1") (pinfunction "1_1") (pintype "passive"))
      (node (ref "R30") (pin "2") (pinfunction "2_2") (pintype "passive"))
      (node (ref "X3") (pin "2") (pinfunction "1_2") (pintype "passive"))
    )
    (net (code "35") (name "Net-(IC4-B)") (class "Default")
      (node (ref "IC4") (pin "7") (pinfunction "B_7") (pintype "bidirectional"))
      (node (ref "R19") (pin "2") (pinfunction "2_2") (pintype "passive"))
      (node (ref "R9") (pin "2") (pinfunction "2_2") (pintype "passive"))
      (node (ref "X3") (pin "3") (pinfunction "1_3") (pintype "passive"))
    )
    (net (code "36") (name "Net-(IC4-DE)") (class "Default")
      (node (ref "IC4") (pin "2") (pinfunction "RE_2") (pintype "bidirectional"))
      (node (ref "IC4") (pin "3") (pinfunction "DE_3") (pintype "bidirectional"))
      (node (ref "OK2") (pin "6") (pinfunction "VO_6") (pintype "passive"))
      (node (ref "R16") (pin "1") (pinfunction "1_1") (pintype "passive"))
    )
    (net (code "37") (name "Net-(IC4-DI)") (class "Default")
      (node (ref "IC4") (pin "4") (pinfunction "DI_4") (pintype "bidirectional"))
      (node (ref "OK3") (pin "6") (pinfunction "VO_6") (pintype "passive"))
      (node (ref "R17") (pin "1") (pinfunction "1_1") (pintype "passive"))
    )
    (net (code "38") (name "Net-(IC4-GND)") (class "Default")
      (node (ref "C17") (pin "-") (pinfunction "-_-") (pintype "passive"))
      (node (ref "C18") (pin "2") (pinfunction "2_2") (pintype "passive"))
      (node (ref "C22") (pin "-") (pinfunction "-_-") (pintype "passive"))
      (node (ref "IC4") (pin "5") (pinfunction "GND_5") (pintype "bidirectional"))
      (node (ref "IC8") (pin "2") (pinfunction "GND_2") (pintype "passive"))
      (node (ref "OK2") (pin "5") (pinfunction "GND_5") (pintype "passive"))
      (node (ref "OK3") (pin "5") (pinfunction "GND_5") (pintype "passive"))
      (node (ref "R9") (pin "1") (pinfunction "1_1") (pintype "passive"))
      (node (ref "X3") (pin "1") (pinfunction "1_1") (pintype "passive"))
    )
    (net (code "39") (name "Net-(IC4-RO)") (class "Default")
      (node (ref "IC4") (pin "1") (pinfunction "RO_1") (pintype "bidirectional"))
      (node (ref "R18") (pin "1") (pinfunction "1_1") (pintype "passive"))
    )
    (net (code "40") (name "Net-(IC4-VCC)") (class "Default")
      (node (ref "C17") (pin "+") (pinfunction "+_+") (pintype "passive"))
      (node (ref "C18") (pin "1") (pinfunction "1_1") (pintype "passive"))
      (node (ref "IC4") (pin "8") (pinfunction "VCC_8") (pintype "bidirectional"))
      (node (ref "IC8") (pin "3") (pinfunction "VO_3") (pintype "passive"))
      (node (ref "OK1") (pin "2") (pinfunction "A_2") (pintype "passive"))
      (node (ref "OK2") (pin "8") (pinfunction "VCC_8") (pintype "passive"))
      (node (ref "OK3") (pin "8") (pinfunction "VCC_8") (pintype "passive"))
      (node (ref "R16") (pin "2") (pinfunction "2_2") (pintype "passive"))
      (node (ref "R17") (pin "2") (pinfunction "2_2") (pintype "passive"))
      (node (ref "R30") (pin "1") (pinfunction "1_1") (pintype "passive"))
      (node (ref "X3") (pin "4") (pinfunction "1_4") (pintype "passive"))
    )
    (net (code "41") (name "Net-(IC5A--IN)") (class "Default")
      (node (ref "C19") (pin "2") (pinfunction "2_2") (pintype "passive"))
      (node (ref "IC5") (pin "2") (pinfunction "-IN_2") (pintype "input"))
      (node (ref "IC6") (pin "6") (pinfunction "C2_6") (pintype "passive"))
      (node (ref "R20") (pin "1") (pinfunction "1_1") (pintype "passive"))
    )
    (net (code "42") (name "Net-(IC5B-+IN)") (class "Default")
      (node (ref "IC5") (pin "5") (pinfunction "+IN_5") (pintype "input"))
      (node (ref "R31") (pin "2") (pinfunction "2_2") (pintype "passive"))
      (node (ref "R32") (pin "1") (pinfunction "1_1") (pintype "passive"))
    )
    (net (code "43") (name "Net-(IC5B--IN)") (class "Default")
      (node (ref "IC5") (pin "6") (pinfunction "-IN_6") (pintype "input"))
      (node (ref "IC5") (pin "7") (pinfunction "OUT_7") (pintype "output"))
    )
    (net (code "44") (name "Net-(IC6-A)") (class "Default")
      (node (ref "C20") (pin "1") (pinfunction "1_1") (pintype "passive"))
      (node (ref "IC6") (pin "2") (pinfunction "A_2") (pintype "passive"))
      (node (ref "IC7") (pin "7") (pinfunction "OUT_7") (pintype "output"))
    )
    (net (code "45") (name "Net-(IC6-A1)") (class "Default")
      (node (ref "C20") (pin "2") (pinfunction "2_2") (pintype "passive"))
      (node (ref "IC6") (pin "4") (pinfunction "A1_4") (pintype "passive"))
      (node (ref "IC7") (pin "6") (pinfunction "-IN_6") (pintype "input"))
      (node (ref "R21") (pin "2") (pinfunction "2_2") (pintype "passive"))
    )
    (net (code "46") (name "Net-(IC6-C)") (class "Default")
      (node (ref "C21") (pin "1") (pinfunction "1_1") (pintype "passive"))
      (node (ref "D11") (pin "A") (pinfunction "A_A") (pintype "passive"))
      (node (ref "IC6") (pin "1") (pinfunction "C_1") (pintype "passive"))
      (node (ref "IC6") (pin "3") (pinfunction "C1_3") (pintype "passive"))
      (node (ref "IC7") (pin "4") (pinfunction "V-_4") (pintype "power_in"))
      (node (ref "R22") (pin "1") (pinfunction "1_1") (pintype "passive"))
      (node (ref "R24") (pin "1") (pinfunction "1_1") (pintype "passive"))
      (node (ref "R34") (pin "1") (pinfunction "1_1") (pintype "passive"))
    )
    (net (code "47") (name "Net-(IC7A-+IN)") (class "Default")
      (node (ref "IC7") (pin "3") (pinfunction "+IN_3") (pintype "input"))
      (node (ref "R33") (pin "1") (pinfunction "1_1") (pintype "passive"))
      (node (ref "R34") (pin "2") (pinfunction "2_2") (pintype "passive"))
    )
    (net (code "48") (name "Net-(IC7A--IN)") (class "Default")
      (node (ref "IC7") (pin "1") (pinfunction "OUT_1") (pintype "output"))
      (node (ref "IC7") (pin "2") (pinfunction "-IN_2") (pintype "input"))
    )
    (net (code "49") (name "Net-(IC7B-+IN)") (class "Default")
      (node (ref "IC7") (pin "5") (pinfunction "+IN_5") (pintype "input"))
      (node (ref "R22") (pin "2") (pinfunction "2_2") (pintype "passive"))
    )
    (net (code "50") (name "Net-(IC7C-V+)") (class "Default")
      (node (ref "C21") (pin "2") (pinfunction "2_2") (pintype "passive"))
      (node (ref "D11") (pin "C") (pinfunction "C_C") (pintype "passive"))
      (node (ref "D12") (pin "C") (pinfunction "C_C") (pintype "passive"))
      (node (ref "D14") (pin "C") (pinfunction "C_C") (pintype "passive"))
      (node (ref "IC7") (pin "8") (pinfunction "V+_8") (pintype "power_in"))
      (node (ref "R33") (pin "2") (pinfunction "2_2") (pintype "passive"))
    )
    (net (code "51") (name "Net-(IC8-VI)") (class "Default")
      (node (ref "C22") (pin "+") (pinfunction "+_+") (pintype "passive"))
      (node (ref "IC8") (pin "1") (pinfunction "VI_1") (pintype "input"))
      (node (ref "R26") (pin "2") (pinfunction "2_2") (pintype "passive"))
    )
    (net (code "52") (name "Net-(JP7-Pad2)") (class "Default")
      (node (ref "JP7") (pin "2") (pinfunction "2_2") (pintype "passive"))
      (node (ref "R19") (pin "1") (pinfunction "1_1") (pintype "passive"))
    )
    (net (code "53") (name "Net-(LED1-PadA)") (class "Default")
      (node (ref "LED1") (pin "A") (pinfunction "A_A") (pintype "passive"))
      (node (ref "R10") (pin "1") (pinfunction "1_1") (pintype "passive"))
    )
    (net (code "54") (name "Net-(LED2-PadA)") (class "Default")
      (node (ref "LED2") (pin "A") (pinfunction "A_A") (pintype "passive"))
      (node (ref "R23") (pin "1") (pinfunction "1_1") (pintype "passive"))
    )
    (net (code "55") (name "Net-(LED3-PadA)") (class "Default")
      (node (ref "LED3") (pin "A") (pinfunction "A_A") (pintype "passive"))
      (node (ref "R25") (pin "1") (pinfunction "1_1") (pintype "passive"))
    )
    (net (code "56") (name "Net-(OK1-C)") (class "Default")
      (node (ref "OK1") (pin "3") (pinfunction "C_3") (pintype "passive"))
      (node (ref "R18") (pin "2") (pinfunction "2_2") (pintype "passive"))
    )
    (net (code "57") (name "Net-(OK2-C)") (class "Default")
      (node (ref "OK2") (pin "3") (pinfunction "C_3") (pintype "passive"))
      (node (ref "R14") (pin "1") (pinfunction "1_1") (pintype "passive"))
    )
    (net (code "58") (name "Net-(OK3-C)") (class "Default")
      (node (ref "OK3") (pin "3") (pinfunction "C_3") (pintype "passive"))
      (node (ref "R15") (pin "1") (pinfunction "1_1") (pintype "passive"))
    )
    (net (code "59") (name "Net-(Q2-PadB)") (class "Default")
      (node (ref "Q2") (pin "B") (pinfunction "B_B") (pintype "passive"))
      (node (ref "R8") (pin "2") (pinfunction "2_2") (pintype "passive"))
      (node (ref "T1") (pin "B") (pinfunction "B_B") (pintype "passive"))
      (node (ref "T2") (pin "C") (pinfunction "C_C") (pintype "passive"))
    )
    (net (code "60") (name "Net-(Q2-PadE)") (class "Default")
      (node (ref "Q2") (pin "E") (pinfunction "E_E") (pintype "passive"))
      (node (ref "R11") (pin "1") (pinfunction "1_1") (pintype "passive"))
      (node (ref "T1") (pin "E") (pinfunction "E_E") (pintype "passive"))
    )
    (net (code "61") (name "Net-(R7-Pad1)") (class "Default")
      (node (ref "R7") (pin "1") (pinfunction "1_1") (pintype "passive"))
      (node (ref "T2") (pin "B") (pinfunction "B_B") (pintype "passive"))
    )
    (net (code "62") (name "Net-(U1-FILTER)") (class "Default")
      (node (ref "C9") (pin "1") (pinfunction "1_1") (pintype "passive"))
      (node (ref "U1") (pin "6") (pinfunction "FILTER_6") (pintype "passive"))
    )
    (net (code "63") (name "Net-(X2B-1)") (class "Default")
      (node (ref "U1") (pin "1") (pinfunction "IP+_1") (pintype "input"))
      (node (ref "U1") (pin "2") (pinfunction "IP+_2") (pintype "input"))
      (node (ref "X2") (pin "2") (pinfunction "1_2") (pintype "passive"))
    )
    (net (code "64") (name "Net-(X3E-1)") (class "Default")
      (node (ref "D16") (pin "A") (pinfunction "A_A") (pintype "passive"))
      (node (ref "X3") (pin "5") (pinfunction "1_5") (pintype "passive"))
    )
    (net (code "65") (name "Net-(X4B-1)") (class "Default")
      (node (ref "D12") (pin "A") (pinfunction "A_A") (pintype "passive"))
      (node (ref "D13") (pin "C") (pinfunction "C_C") (pintype "passive"))
      (node (ref "X4") (pin "2") (pinfunction "1_2") (pintype "passive"))
    )
    (net (code "66") (name "Net-(X6B-1)") (class "Default")
      (node (ref "D5") (pin "A") (pinfunction "A_A") (pintype "passive"))
      (node (ref "D6") (pin "C") (pinfunction "C_C") (pintype "passive"))
      (node (ref "X6") (pin "2") (pinfunction "1_2") (pintype "passive"))
    )
    (net (code "67") (name "PWM") (class "Default")
      (node (ref "IC3") (pin "15") (pinfunction "PB1(OC1A)_15") (pintype "bidirectional"))
      (node (ref "R28") (pin "2") (pinfunction "2_2") (pintype "passive"))
      (node (ref "R7") (pin "2") (pinfunction "2_2") (pintype "passive"))
    )
    (net (code "68") (name "RESET") (class "Default")
      (node (ref "C13") (pin "+") (pinfunction "+_+") (pintype "passive"))
      (node (ref "IC3") (pin "1") (pinfunction "PC6(/RESET)_1") (pintype "bidirectional"))
      (node (ref "J1") (pin "5") (pinfunction "5_5") (pintype "passive"))
      (node (ref "R12") (pin "1") (pinfunction "1_1") (pintype "passive"))
    )
    (net (code "69") (name "RX") (class "Default")
      (node (ref "IC3") (pin "2") (pinfunction "PD0(RXD)_2") (pintype "bidirectional"))
      (node (ref "OK1") (pin "6") (pinfunction "VO_6") (pintype "passive"))
      (node (ref "R13") (pin "1") (pinfunction "1_1") (pintype "passive"))
    )
    (net (code "70") (name "TX") (class "Default")
      (node (ref "IC3") (pin "3") (pinfunction "PD1(TXD)_3") (pintype "bidirectional"))
      (node (ref "R15") (pin "2") (pinfunction "2_2") (pintype "passive"))
    )
    (net (code "71") (name "TX_EN") (class "Default")
      (node (ref "IC3") (pin "4") (pinfunction "PD2(INT0)_4") (pintype "bidirectional"))
      (node (ref "R14") (pin "2") (pinfunction "2_2") (pintype "passive"))
    )
    (net (code "72") (name "unconnected-(IC3-PB2(SS{slash}OC1B)-Pad16)") (class "Default")
      (node (ref "IC3") (pin "16") (pinfunction "PB2(SS/OC1B)_16") (pintype "bidirectional"))
    )
    (net (code "73") (name "unconnected-(IC3-PC2(ADC2)-Pad25)") (class "Default")
      (node (ref "IC3") (pin "25") (pinfunction "PC2(ADC2)_25") (pintype "bidirectional"))
    )
    (net (code "74") (name "unconnected-(IC3-PC3(ADC3)-Pad26)") (class "Default")
      (node (ref "IC3") (pin "26") (pinfunction "PC3(ADC3)_26") (pintype "bidirectional"))
    )
    (net (code "75") (name "unconnected-(IC3-PD3(INT1)-Pad5)") (class "Default")
      (node (ref "IC3") (pin "5") (pinfunction "PD3(INT1)_5") (pintype "bidirectional"))
    )
    (net (code "76") (name "unconnected-(IC3-PD4(XCK{slash}T0)-Pad6)") (class "Default")
      (node (ref "IC3") (pin "6") (pinfunction "PD4(XCK/T0)_6") (pintype "bidirectional"))
    )
    (net (code "77") (name "unconnected-(J1-Pad6)") (class "Default")
      (node (ref "J1") (pin "6") (pinfunction "6_6") (pintype "passive"))
    )
    (net (code "78") (name "unconnected-(OK1-VE-Pad7)") (class "Default")
      (node (ref "OK1") (pin "7") (pinfunction "VE_7") (pintype "passive"))
    )
    (net (code "79") (name "unconnected-(OK2-VE-Pad7)") (class "Default")
      (node (ref "OK2") (pin "7") (pinfunction "VE_7") (pintype "passive"))
    )
    (net (code "80") (name "unconnected-(OK3-VE-Pad7)") (class "Default")
      (node (ref "OK3") (pin "7") (pinfunction "VE_7") (pintype "passive"))
    )
    (net (code "81") (name "unconnected-(X5C-S-Pad3)") (class "Default")
      (node (ref "X5") (pin "3") (pinfunction "S_3") (pintype "passive"))
    )
  )
)
